# GB-WP-D1.net
KiCad netlist of a schematic drawn in EAGLE
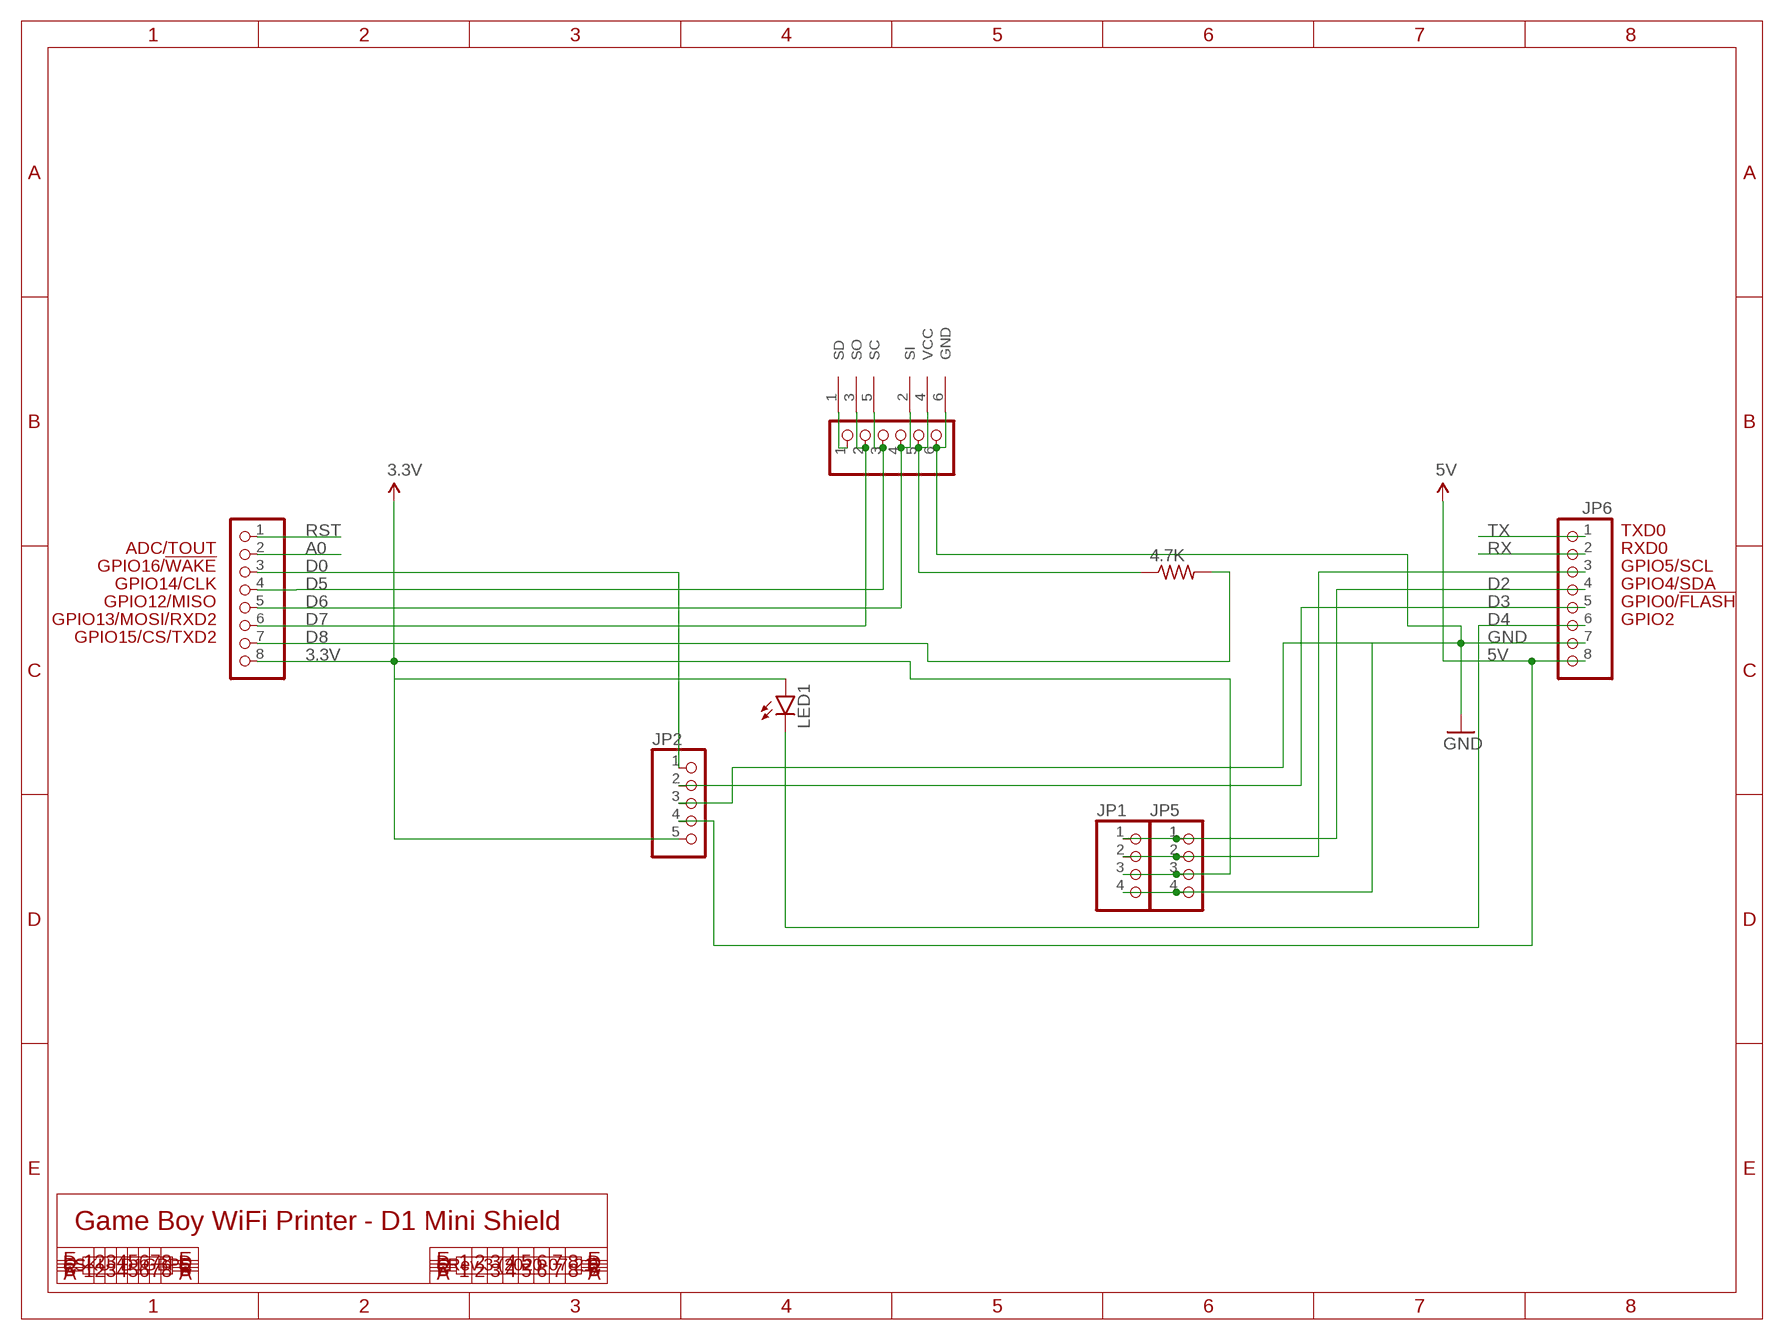
[diagram p0: schematic, sheet 1]

(export (version "E")
  (design (tool "Eeschema 10.0.6"))
  (components
    (comp (ref "4.7K")
      (value "R-US_0207/10")
      (footprint "eagle-import:0207_10")
      (libsource (lib "eagle-import") (part "R-US_0207/10"))
    )
    (comp (ref "JP1")
      (value "PINHD-1X4/OCT")
      (footprint "eagle-import:1X04_OCT")
      (libsource (lib "eagle-import") (part "PINHD-1X4/OCT"))
    )
    (comp (ref "JP2")
      (value "PINHD-1X5/OCT")
      (footprint "eagle-import:1X05_OCT")
      (libsource (lib "eagle-import") (part "PINHD-1X5/OCT"))
    )
    (comp (ref "JP3")
      (value "PINHD-1X8/OCT")
      (footprint "eagle-import:1X08_OCT")
      (libsource (lib "eagle-import") (part "PINHD-1X8/OCT"))
    )
    (comp (ref "JP4")
      (value "PINHD-1X6/OCT")
      (footprint "eagle-import:1X06_OCT")
      (libsource (lib "eagle-import") (part "PINHD-1X6/OCT"))
    )
    (comp (ref "JP5")
      (value "PINHD-1X4/OCT")
      (footprint "eagle-import:1X04_OCT")
      (libsource (lib "eagle-import") (part "PINHD-1X4/OCT"))
    )
    (comp (ref "JP6")
      (value "PINHD-1X8/OCT")
      (footprint "eagle-import:1X08_OCT")
      (libsource (lib "eagle-import") (part "PINHD-1X8/OCT"))
    )
    (comp (ref "LED1")
      (value "LED3MM")
      (footprint "eagle-import:LED3MM")
      (libsource (lib "eagle-import") (part "LED3MM"))
    )
    (comp (ref "U$2")
      (value "GB-LINK-PADS")
      (footprint "eagle-import:GB-LINK-PCB")
      (libsource (lib "eagle-import") (part "GB-LINK-PADS"))
    )
  )
  (nets
    (net (code "1") (name "/A0") (class "Default")
      (node (ref "JP3") (pin "2") (pinfunction "2_2") (pintype "passive"))
    )
    (net (code "2") (name "/D0") (class "Default")
      (node (ref "JP2") (pin "1") (pinfunction "1_1") (pintype "passive"))
      (node (ref "JP3") (pin "3") (pinfunction "3_3") (pintype "passive"))
    )
    (net (code "3") (name "/D2") (class "Default")
      (node (ref "JP1") (pin "1") (pinfunction "1_1") (pintype "passive"))
      (node (ref "JP5") (pin "1") (pinfunction "1_1") (pintype "passive"))
      (node (ref "JP6") (pin "4") (pinfunction "4_4") (pintype "passive"))
    )
    (net (code "4") (name "/D3") (class "Default")
      (node (ref "JP2") (pin "2") (pinfunction "2_2") (pintype "passive"))
      (node (ref "JP6") (pin "5") (pinfunction "5_5") (pintype "passive"))
    )
    (net (code "5") (name "/D4") (class "Default")
      (node (ref "JP6") (pin "6") (pinfunction "6_6") (pintype "passive"))
      (node (ref "LED1") (pin "K") (pinfunction "C_K") (pintype "passive"))
    )
    (net (code "6") (name "/D5") (class "Default")
      (node (ref "JP3") (pin "4") (pinfunction "4_4") (pintype "passive"))
      (node (ref "JP4") (pin "3") (pinfunction "3_3") (pintype "passive"))
      (node (ref "U$2") (pin "5") (pinfunction "SC_5") (pintype "bidirectional"))
    )
    (net (code "7") (name "/D6") (class "Default")
      (node (ref "JP3") (pin "5") (pinfunction "5_5") (pintype "passive"))
      (node (ref "JP4") (pin "4") (pinfunction "4_4") (pintype "passive"))
      (node (ref "U$2") (pin "2") (pinfunction "SI_2") (pintype "bidirectional"))
    )
    (net (code "8") (name "/D7") (class "Default")
      (node (ref "JP3") (pin "6") (pinfunction "6_6") (pintype "passive"))
      (node (ref "JP4") (pin "2") (pinfunction "2_2") (pintype "passive"))
      (node (ref "U$2") (pin "3") (pinfunction "SO_3") (pintype "bidirectional"))
    )
    (net (code "9") (name "/D8") (class "Default")
      (node (ref "4.7K") (pin "2") (pinfunction "2_2") (pintype "passive"))
      (node (ref "JP3") (pin "7") (pinfunction "7_7") (pintype "passive"))
    )
    (net (code "10") (name "/RST") (class "Default")
      (node (ref "JP3") (pin "1") (pinfunction "1_1") (pintype "passive"))
    )
    (net (code "11") (name "/RX") (class "Default")
      (node (ref "JP6") (pin "2") (pinfunction "2_2") (pintype "passive"))
    )
    (net (code "12") (name "/TX") (class "Default")
      (node (ref "JP6") (pin "1") (pinfunction "1_1") (pintype "passive"))
    )
    (net (code "13") (name "3.3V") (class "Default")
      (node (ref "JP1") (pin "3") (pinfunction "3_3") (pintype "passive"))
      (node (ref "JP2") (pin "5") (pinfunction "5_5") (pintype "passive"))
      (node (ref "JP3") (pin "8") (pinfunction "8_8") (pintype "passive"))
      (node (ref "JP5") (pin "3") (pinfunction "3_3") (pintype "passive"))
      (node (ref "LED1") (pin "A") (pinfunction "A_A") (pintype "passive"))
    )
    (net (code "14") (name "5V") (class "Default")
      (node (ref "JP2") (pin "4") (pinfunction "4_4") (pintype "passive"))
      (node (ref "JP6") (pin "8") (pinfunction "8_8") (pintype "passive"))
    )
    (net (code "15") (name "GND") (class "Default")
      (node (ref "JP1") (pin "4") (pinfunction "4_4") (pintype "passive"))
      (node (ref "JP2") (pin "3") (pinfunction "3_3") (pintype "passive"))
      (node (ref "JP4") (pin "6") (pinfunction "6_6") (pintype "passive"))
      (node (ref "JP5") (pin "4") (pinfunction "4_4") (pintype "passive"))
      (node (ref "JP6") (pin "7") (pinfunction "7_7") (pintype "passive"))
      (node (ref "U$2") (pin "6") (pinfunction "GND_6") (pintype "bidirectional"))
    )
    (net (code "16") (name "Net-(JP1-Pad2)") (class "Default")
      (node (ref "JP1") (pin "2") (pinfunction "2_2") (pintype "passive"))
      (node (ref "JP5") (pin "2") (pinfunction "2_2") (pintype "passive"))
      (node (ref "JP6") (pin "3") (pinfunction "3_3") (pintype "passive"))
    )
    (net (code "17") (name "Net-(U$2-SD)") (class "Default")
      (node (ref "JP4") (pin "1") (pinfunction "1_1") (pintype "passive"))
      (node (ref "U$2") (pin "1") (pinfunction "SD_1") (pintype "bidirectional"))
    )
    (net (code "18") (name "Net-(U$2-VCC)") (class "Default")
      (node (ref "4.7K") (pin "1") (pinfunction "1_1") (pintype "passive"))
      (node (ref "JP4") (pin "5") (pinfunction "5_5") (pintype "passive"))
      (node (ref "U$2") (pin "4") (pinfunction "VCC_4") (pintype "bidirectional"))
    )
  )
)
